# 02_CM4_Module.net
KiCad netlist of a schematic drawn in Altium Designer
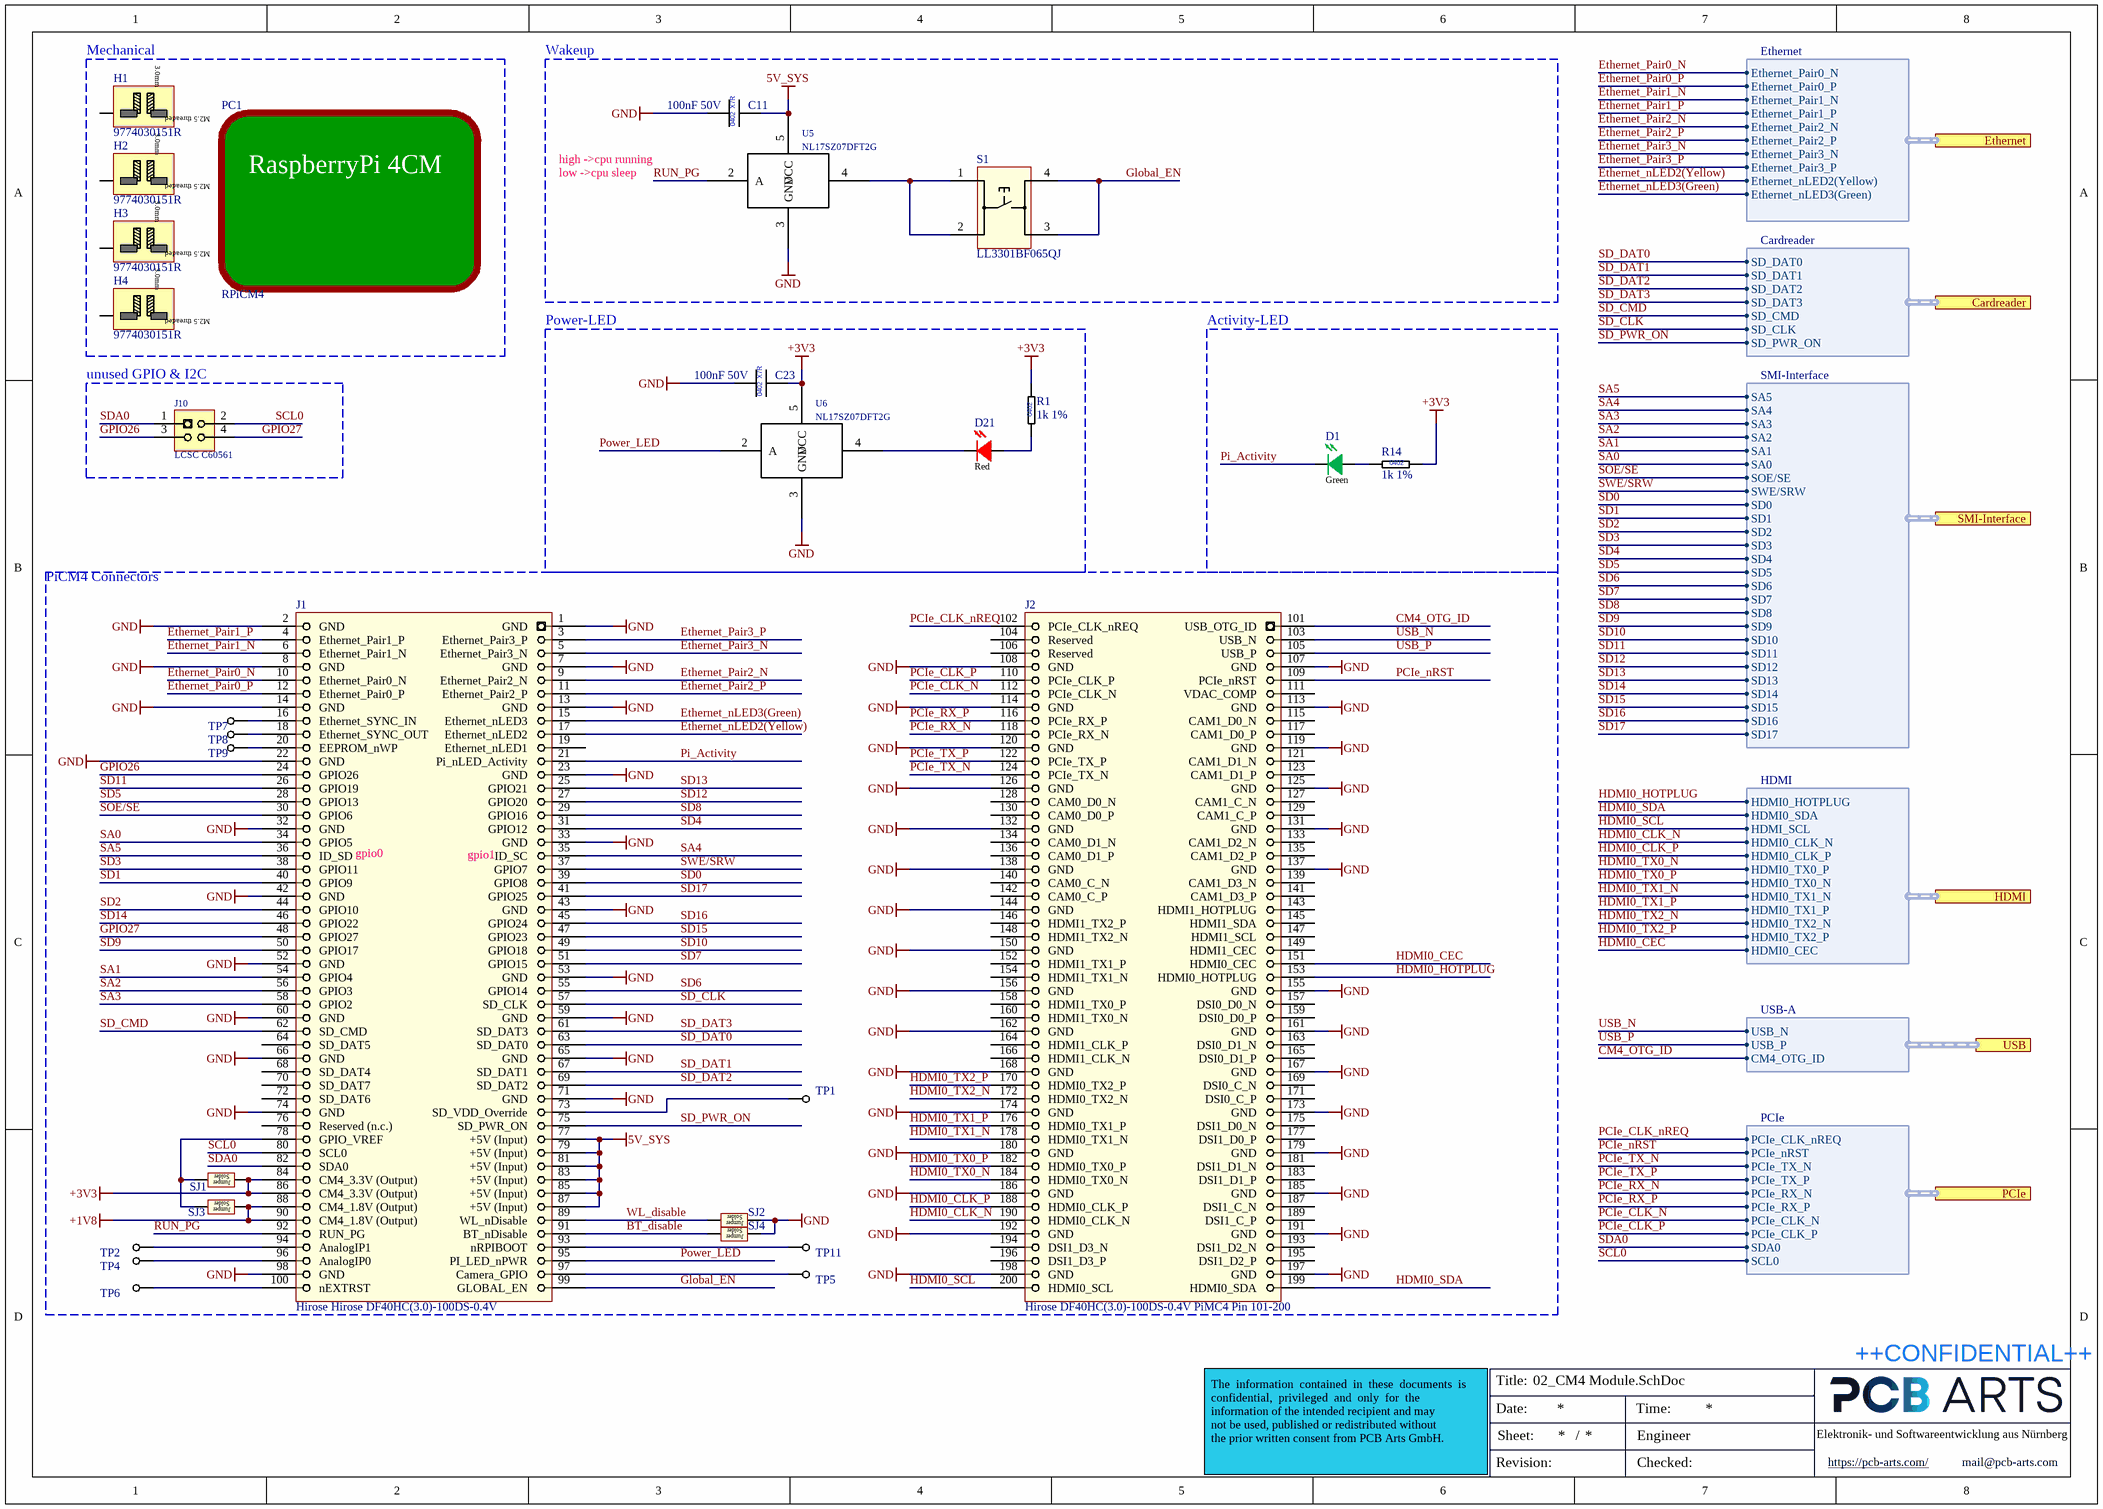
[diagram p0: 02_CM4 Module.SchDoc]

(export (version "E")
  (design (tool "Eeschema 10.0.6"))
  (components
    (comp (ref "C11")
      (value "100nF 50V")
      (footprint "AlemNano 201029:CAP_0402")
      (description "Multilayer Ceramic Capacitors MLCC - SMD/SMT 0402 50VDC")
      (libsource (lib "AlemNano 201029") (part "CAP_0402_100nF_50V"))
    )
    (comp (ref "C23")
      (value "100nF 50V")
      (footprint "AlemNano 201029:CAP_0402")
      (description "Multilayer Ceramic Capacitors MLCC - SMD/SMT 0402 50VDC")
      (libsource (lib "AlemNano 201029") (part "CAP_0402_100nF_50V"))
    )
    (comp (ref "D1")
      (value "LTST-S270KGKT")
      (footprint "Active:LED-0603 Sideview")
      (description "GREEN  0603 Light Emitting Diode")
      (fields (field (name "COLOR") "Green"))
      (libsource (lib "Active") (part "LED 0603 Green Sideview"))
    )
    (comp (ref "D21")
      (value "LTST-S270KRKT")
      (footprint "Active:LED-0603 Sideview")
      (description "RED  0603 Light Emitting Diode")
      (fields (field (name "COLOR") "Red"))
      (libsource (lib "Active") (part "LED 0603 Red Sideview"))
    )
    (comp (ref "H1")
      (value "9774030151R")
      (footprint "Electro_Mech:9774030151R")
      (description "Würth Standoff M2.5 h:3.0mm 9774030151R")
      (libsource (lib "Electro_Mech") (part "Würth Standoff M2.5 h{colon}3.0mm"))
    )
    (comp (ref "H2")
      (value "9774030151R")
      (footprint "Electro_Mech:9774030151R")
      (description "Würth Standoff M2.5 h:3.0mm 9774030151R")
      (libsource (lib "Electro_Mech") (part "Würth Standoff M2.5 h{colon}3.0mm"))
    )
    (comp (ref "H3")
      (value "9774030151R")
      (footprint "Electro_Mech:9774030151R")
      (description "Würth Standoff M2.5 h:3.0mm 9774030151R")
      (libsource (lib "Electro_Mech") (part "Würth Standoff M2.5 h{colon}3.0mm"))
    )
    (comp (ref "H4")
      (value "9774030151R")
      (footprint "Electro_Mech:9774030151R")
      (description "Würth Standoff M2.5 h:3.0mm 9774030151R")
      (libsource (lib "Electro_Mech") (part "Würth Standoff M2.5 h{colon}3.0mm"))
    )
    (comp (ref "J1")
      (value "Hirose Hirose DF40HC(3.0)-100DS-0.4V")
      (footprint "conn:Hirose DF40HC(3.0)-100DS-0.4V_1-100")
      (description "Hirose DF40HC(3.0)-100DS-0.4V 3mm heigth receptacle for Raspberry Pi CM4, Pin 1-100")
      (libsource (lib "Conn") (part "DF40HC(3.0)-100DS-0.4V RPiCM4 Pin 1-100"))
    )
    (comp (ref "J2")
      (value "Hirose DF40HC(3.0)-100DS-0.4V PiMC4 Pin 101-200")
      (footprint "Conn:Hirose DF40HC(3.0)-100DS-0.4V_PiCM4_101_200")
      (description "Hirose DF40C-100DS-0.4V 3mm heigth receptacle for Raspberry Pi CM4, Pin 101-200")
      (libsource (lib "Conn") (part "DF40HC(3.0)-100DS-0.4V RPiCM4 Pin 101-200"))
    )
    (comp (ref "J10")
      (value "LCSC C60561")
      (footprint "conn:LCSC C60561")
      (description "Pin header 2.54mm 4Pol right angle")
      (libsource (lib "Conn") (part "LCSC C60561_Pin header 2.54mm 4Pol right angle"))
    )
    (comp (ref "PC1")
      (value "RPiCM4")
      (footprint "Mechanical:RaspberryPi_CM4")
      (description "Raspberry Pi 4 Compute Module 4")
      (libsource (lib "Mechanical") (part "Raspberry Pi Compute Module 4"))
    )
    (comp (ref "R1")
      (value "1k 1%")
      (footprint "res:RES_0402")
      (description "Thick Film Resistors - SMD 1kOhm 1%")
      (libsource (lib "Res") (part "RES_0402_1k_1%"))
    )
    (comp (ref "R14")
      (value "1k 1%")
      (footprint "res:RES_0402")
      (description "Thick Film Resistors - SMD 1kOhm 1%")
      (libsource (lib "Res") (part "RES_0402_1k_1%"))
    )
    (comp (ref "S1")
      (value "LL3301BF065QJ")
      (footprint "Electro_Mech:LL3301BF065QJ")
      (description "SPST Top Actuated  Button, 65gf, SMD h: 9.8mm")
      (libsource (lib "Electro_Mech") (part "LL3301BF065QJ_SPST Top Actuated  Button, 65gf, SMD h{colon} 9.8mm"))
    )
    (comp (ref "SJ1")
      (value "Solderbridge_0402")
      (footprint "Conn:Solderbridge_0402")
      (libsource (lib "Conn") (part "Solderbridge_0402"))
    )
    (comp (ref "SJ2")
      (value "Solderbridge_0402")
      (footprint "Conn:Solderbridge_0402")
      (libsource (lib "Conn") (part "Solderbridge_0402"))
    )
    (comp (ref "SJ3")
      (value "Solderbridge_0402")
      (footprint "Conn:Solderbridge_0402")
      (libsource (lib "Conn") (part "Solderbridge_0402"))
    )
    (comp (ref "SJ4")
      (value "Solderbridge_0402")
      (footprint "Conn:Solderbridge_0402")
      (libsource (lib "Conn") (part "Solderbridge_0402"))
    )
    (comp (ref "TP1")
      (value "Testpoint")
      (footprint "Electro_mech:Testpoint 0.8mm")
      (description "Testpoint 0.8mm")
      (libsource (lib "Electro_Mech") (part "Testpoint 0.8mm"))
    )
    (comp (ref "TP2")
      (value "Testpoint")
      (footprint "Electro_mech:Testpoint 0.8mm")
      (description "Testpoint 0.8mm")
      (libsource (lib "Electro_Mech") (part "Testpoint 0.8mm"))
    )
    (comp (ref "TP4")
      (value "Testpoint")
      (footprint "Electro_mech:Testpoint 0.8mm")
      (description "Testpoint 0.8mm")
      (libsource (lib "Electro_Mech") (part "Testpoint 0.8mm"))
    )
    (comp (ref "TP5")
      (value "Testpoint")
      (footprint "Electro_mech:Testpoint 0.8mm")
      (description "Testpoint 0.8mm")
      (libsource (lib "Electro_Mech") (part "Testpoint 0.8mm"))
    )
    (comp (ref "TP6")
      (value "Testpoint")
      (footprint "Electro_mech:Testpoint 0.8mm")
      (description "Testpoint 0.8mm")
      (libsource (lib "Electro_Mech") (part "Testpoint 0.8mm"))
    )
    (comp (ref "TP7")
      (value "Testpoint")
      (footprint "Electro_mech:Testpoint 0.8mm")
      (description "Testpoint 0.8mm")
      (libsource (lib "Electro_Mech") (part "Testpoint 0.8mm"))
    )
    (comp (ref "TP8")
      (value "Testpoint")
      (footprint "Electro_mech:Testpoint 0.8mm")
      (description "Testpoint 0.8mm")
      (libsource (lib "Electro_Mech") (part "Testpoint 0.8mm"))
    )
    (comp (ref "TP9")
      (value "Testpoint")
      (footprint "Electro_mech:Testpoint 0.8mm")
      (description "Testpoint 0.8mm")
      (libsource (lib "Electro_Mech") (part "Testpoint 0.8mm"))
    )
    (comp (ref "TP11")
      (value "Testpoint")
      (footprint "Electro_mech:Testpoint 0.8mm")
      (description "Testpoint 0.8mm")
      (libsource (lib "Electro_Mech") (part "Testpoint 0.8mm"))
    )
    (comp (ref "U5")
      (value "NL17SZ07DFT2G")
      (footprint "Digital:SOT65P210X110-5N")
      (description "Puffer u. Leitungstreiber 1.65-5.5V Single Non-Inverting")
      (libsource (lib "Digital") (part "NL17SZ07DFT2G_Buffer 1.65-5.5V Single Non-Inverting"))
    )
    (comp (ref "U6")
      (value "NL17SZ07DFT2G")
      (footprint "Digital:SOT65P210X110-5N")
      (description "Puffer u. Leitungstreiber 1.65-5.5V Single Non-Inverting")
      (libsource (lib "Digital") (part "NL17SZ07DFT2G_Buffer 1.65-5.5V Single Non-Inverting"))
    )
  )
  (nets
    (net (code "7") (name "+1V8") (class "Default")
      (node (ref "J1") (pin "88") (pinfunction "CM4_1.8V_(Output)_88") (pintype "passive"))
      (node (ref "J1") (pin "90") (pinfunction "CM4_1.8V_(Output)_90") (pintype "passive"))
      (node (ref "SJ3") (pin "2") (pinfunction "2_2") (pintype "passive"))
    )
    (net (code "8") (name "+3V3") (class "Default")
      (node (ref "C23") (pin "2") (pinfunction "2_2") (pintype "passive"))
      (node (ref "J1") (pin "84") (pinfunction "CM4_3.3V_(Output)_84") (pintype "passive"))
      (node (ref "J1") (pin "86") (pinfunction "CM4_3.3V_(Output)_86") (pintype "passive"))
      (node (ref "R1") (pin "2") (pinfunction "2_2") (pintype "passive"))
      (node (ref "R14") (pin "2") (pinfunction "2_2") (pintype "passive"))
      (node (ref "SJ1") (pin "2") (pinfunction "2_2") (pintype "passive"))
      (node (ref "U6") (pin "5") (pinfunction "VCC_5") (pintype "passive"))
    )
    (net (code "9") (name "/BT_disable") (class "Default")
      (node (ref "J1") (pin "91") (pinfunction "BT_nDisable_91") (pintype "passive"))
      (node (ref "SJ4") (pin "1") (pinfunction "1_1") (pintype "passive"))
    )
    (net (code "10") (name "/CM4_OTG_ID") (class "Default")
      (node (ref "J2") (pin "101") (pinfunction "USB_OTG_ID_101") (pintype "passive"))
    )
    (net (code "11") (name "/Ethernet_Pair0_N") (class "Default")
      (node (ref "J1") (pin "10") (pinfunction "Ethernet_Pair0_N_10") (pintype "passive"))
    )
    (net (code "12") (name "/Ethernet_Pair0_P") (class "Default")
      (node (ref "J1") (pin "12") (pinfunction "Ethernet_Pair0_P_12") (pintype "passive"))
    )
    (net (code "13") (name "/Ethernet_Pair1_N") (class "Default")
      (node (ref "J1") (pin "6") (pinfunction "Ethernet_Pair1_N_6") (pintype "passive"))
    )
    (net (code "14") (name "/Ethernet_Pair1_P") (class "Default")
      (node (ref "J1") (pin "4") (pinfunction "Ethernet_Pair1_P_4") (pintype "passive"))
    )
    (net (code "15") (name "/Ethernet_Pair2_N") (class "Default")
      (node (ref "J1") (pin "9") (pinfunction "Ethernet_Pair2_N_9") (pintype "passive"))
    )
    (net (code "16") (name "/Ethernet_Pair2_P") (class "Default")
      (node (ref "J1") (pin "11") (pinfunction "Ethernet_Pair2_P_11") (pintype "passive"))
    )
    (net (code "17") (name "/Ethernet_Pair3_N") (class "Default")
      (node (ref "J1") (pin "5") (pinfunction "Ethernet_Pair3_N_5") (pintype "passive"))
    )
    (net (code "18") (name "/Ethernet_Pair3_P") (class "Default")
      (node (ref "J1") (pin "3") (pinfunction "Ethernet_Pair3_P_3") (pintype "passive"))
    )
    (net (code "19") (name "/Ethernet_nLED2(Yellow)") (class "Default")
      (node (ref "J1") (pin "17") (pinfunction "Ethernet_nLED2_17") (pintype "passive"))
    )
    (net (code "20") (name "/Ethernet_nLED3(Green)") (class "Default")
      (node (ref "J1") (pin "15") (pinfunction "Ethernet_nLED3_15") (pintype "passive"))
    )
    (net (code "21") (name "/GPIO26") (class "Default")
      (node (ref "J1") (pin "24") (pinfunction "GPIO26_24") (pintype "passive"))
      (node (ref "J10") (pin "3") (pinfunction "3_3") (pintype "passive"))
    )
    (net (code "22") (name "/GPIO27") (class "Default")
      (node (ref "J1") (pin "48") (pinfunction "GPIO27_48") (pintype "passive"))
      (node (ref "J10") (pin "4") (pinfunction "4_4") (pintype "passive"))
    )
    (net (code "23") (name "/Global_EN") (class "Default")
      (node (ref "J1") (pin "99") (pinfunction "GLOBAL_EN_99") (pintype "passive"))
      (node (ref "S1") (pin "3") (pinfunction "3_3") (pintype "passive"))
      (node (ref "S1") (pin "4") (pinfunction "4_4") (pintype "passive"))
    )
    (net (code "24") (name "/HDMI0_CEC") (class "Default")
      (node (ref "J2") (pin "151") (pinfunction "HDMI0_CEC_151") (pintype "passive"))
    )
    (net (code "25") (name "/HDMI0_CLK_N") (class "Default")
      (node (ref "J2") (pin "190") (pinfunction "HDMI0_CLK_N_190") (pintype "passive"))
    )
    (net (code "26") (name "/HDMI0_CLK_P") (class "Default")
      (node (ref "J2") (pin "188") (pinfunction "HDMI0_CLK_P_188") (pintype "passive"))
    )
    (net (code "27") (name "/HDMI0_HOTPLUG") (class "Default")
      (node (ref "J2") (pin "153") (pinfunction "HDMI0_HOTPLUG_153") (pintype "passive"))
    )
    (net (code "28") (name "/HDMI0_SCL") (class "Default")
      (node (ref "J2") (pin "200") (pinfunction "HDMI0_SCL_200") (pintype "passive"))
    )
    (net (code "29") (name "/HDMI0_SDA") (class "Default")
      (node (ref "J2") (pin "199") (pinfunction "HDMI0_SDA_199") (pintype "passive"))
    )
    (net (code "30") (name "/HDMI0_TX0_N") (class "Default")
      (node (ref "J2") (pin "184") (pinfunction "HDMI0_TX0_N_184") (pintype "passive"))
    )
    (net (code "31") (name "/HDMI0_TX0_P") (class "Default")
      (node (ref "J2") (pin "182") (pinfunction "HDMI0_TX0_P_182") (pintype "passive"))
    )
    (net (code "32") (name "/HDMI0_TX1_N") (class "Default")
      (node (ref "J2") (pin "178") (pinfunction "HDMI0_TX1_N_178") (pintype "passive"))
    )
    (net (code "33") (name "/HDMI0_TX1_P") (class "Default")
      (node (ref "J2") (pin "176") (pinfunction "HDMI0_TX1_P_176") (pintype "passive"))
    )
    (net (code "34") (name "/HDMI0_TX2_N") (class "Default")
      (node (ref "J2") (pin "172") (pinfunction "HDMI0_TX2_N_172") (pintype "passive"))
    )
    (net (code "35") (name "/HDMI0_TX2_P") (class "Default")
      (node (ref "J2") (pin "170") (pinfunction "HDMI0_TX2_P_170") (pintype "passive"))
    )
    (net (code "36") (name "/PCIe_CLK_N") (class "Default")
      (node (ref "J2") (pin "112") (pinfunction "PCIe_CLK_N_112") (pintype "passive"))
    )
    (net (code "37") (name "/PCIe_CLK_P") (class "Default")
      (node (ref "J2") (pin "110") (pinfunction "PCIe_CLK_P_110") (pintype "passive"))
    )
    (net (code "38") (name "/PCIe_CLK_nREQ") (class "Default")
      (node (ref "J2") (pin "102") (pinfunction "PCIe_CLK_nREQ_102") (pintype "passive"))
    )
    (net (code "39") (name "/PCIe_RX_N") (class "Default")
      (node (ref "J2") (pin "118") (pinfunction "PCIe_RX_N_118") (pintype "passive"))
    )
    (net (code "40") (name "/PCIe_RX_P") (class "Default")
      (node (ref "J2") (pin "116") (pinfunction "PCIe_RX_P_116") (pintype "passive"))
    )
    (net (code "41") (name "/PCIe_TX_N") (class "Default")
      (node (ref "J2") (pin "124") (pinfunction "PCIe_TX_N_124") (pintype "passive"))
    )
    (net (code "42") (name "/PCIe_TX_P") (class "Default")
      (node (ref "J2") (pin "122") (pinfunction "PCIe_TX_P_122") (pintype "passive"))
    )
    (net (code "43") (name "/PCIe_nRST") (class "Default")
      (node (ref "J2") (pin "109") (pinfunction "PCIe_nRST_109") (pintype "passive"))
    )
    (net (code "44") (name "/Pi_Activity") (class "Default")
      (node (ref "D1") (pin "1") (pinfunction "1_1") (pintype "passive"))
      (node (ref "J1") (pin "21") (pinfunction "Pi_nLED_Activity_21") (pintype "passive"))
    )
    (net (code "45") (name "/Power_LED") (class "Default")
      (node (ref "J1") (pin "95") (pinfunction "PI_LED_nPWR_95") (pintype "passive"))
      (node (ref "U6") (pin "2") (pinfunction "A_2") (pintype "passive"))
    )
    (net (code "46") (name "/RUN_PG") (class "Default")
      (node (ref "J1") (pin "92") (pinfunction "RUN_PG_92") (pintype "passive"))
      (node (ref "U5") (pin "2") (pinfunction "A_2") (pintype "passive"))
    )
    (net (code "47") (name "/SA0") (class "Default")
      (node (ref "J1") (pin "34") (pinfunction "GPIO5_34") (pintype "passive"))
    )
    (net (code "48") (name "/SA1") (class "Default")
      (node (ref "J1") (pin "54") (pinfunction "GPIO4_54") (pintype "passive"))
    )
    (net (code "49") (name "/SA2") (class "Default")
      (node (ref "J1") (pin "56") (pinfunction "GPIO3_56") (pintype "passive"))
    )
    (net (code "50") (name "/SA3") (class "Default")
      (node (ref "J1") (pin "58") (pinfunction "GPIO2_58") (pintype "passive"))
    )
    (net (code "51") (name "/SA4") (class "Default")
      (node (ref "J1") (pin "35") (pinfunction "ID_SC_35") (pintype "passive"))
    )
    (net (code "52") (name "/SA5") (class "Default")
      (node (ref "J1") (pin "36") (pinfunction "ID_SD_36") (pintype "passive"))
    )
    (net (code "53") (name "/SCL0") (class "Default")
      (node (ref "J1") (pin "80") (pinfunction "SCL0_80") (pintype "passive"))
      (node (ref "J10") (pin "2") (pinfunction "2_2") (pintype "passive"))
    )
    (net (code "54") (name "/SD0") (class "Default")
      (node (ref "J1") (pin "39") (pinfunction "GPIO8_39") (pintype "passive"))
    )
    (net (code "55") (name "/SD1") (class "Default")
      (node (ref "J1") (pin "40") (pinfunction "GPIO9_40") (pintype "passive"))
    )
    (net (code "56") (name "/SD2") (class "Default")
      (node (ref "J1") (pin "44") (pinfunction "GPIO10_44") (pintype "passive"))
    )
    (net (code "57") (name "/SD3") (class "Default")
      (node (ref "J1") (pin "38") (pinfunction "GPIO11_38") (pintype "passive"))
    )
    (net (code "58") (name "/SD4") (class "Default")
      (node (ref "J1") (pin "31") (pinfunction "GPIO12_31") (pintype "passive"))
    )
    (net (code "59") (name "/SD5") (class "Default")
      (node (ref "J1") (pin "28") (pinfunction "GPIO13_28") (pintype "passive"))
    )
    (net (code "60") (name "/SD6") (class "Default")
      (node (ref "J1") (pin "55") (pinfunction "GPIO14_55") (pintype "passive"))
    )
    (net (code "61") (name "/SD7") (class "Default")
      (node (ref "J1") (pin "51") (pinfunction "GPIO15_51") (pintype "passive"))
    )
    (net (code "62") (name "/SD8") (class "Default")
      (node (ref "J1") (pin "29") (pinfunction "GPIO16_29") (pintype "passive"))
    )
    (net (code "63") (name "/SD9") (class "Default")
      (node (ref "J1") (pin "50") (pinfunction "GPIO17_50") (pintype "passive"))
    )
    (net (code "64") (name "/SD10") (class "Default")
      (node (ref "J1") (pin "49") (pinfunction "GPIO18_49") (pintype "passive"))
    )
    (net (code "65") (name "/SD11") (class "Default")
      (node (ref "J1") (pin "26") (pinfunction "GPIO19_26") (pintype "passive"))
    )
    (net (code "66") (name "/SD12") (class "Default")
      (node (ref "J1") (pin "27") (pinfunction "GPIO20_27") (pintype "passive"))
    )
    (net (code "67") (name "/SD13") (class "Default")
      (node (ref "J1") (pin "25") (pinfunction "GPIO21_25") (pintype "passive"))
    )
    (net (code "68") (name "/SD14") (class "Default")
      (node (ref "J1") (pin "46") (pinfunction "GPIO22_46") (pintype "passive"))
    )
    (net (code "69") (name "/SD15") (class "Default")
      (node (ref "J1") (pin "47") (pinfunction "GPIO23_47") (pintype "passive"))
    )
    (net (code "70") (name "/SD16") (class "Default")
      (node (ref "J1") (pin "45") (pinfunction "GPIO24_45") (pintype "passive"))
    )
    (net (code "71") (name "/SD17") (class "Default")
      (node (ref "J1") (pin "41") (pinfunction "GPIO25_41") (pintype "passive"))
    )
    (net (code "72") (name "/SDA0") (class "Default")
      (node (ref "J1") (pin "82") (pinfunction "SDA0_82") (pintype "passive"))
      (node (ref "J10") (pin "1") (pinfunction "1_1") (pintype "passive"))
    )
    (net (code "73") (name "/SD_CLK") (class "Default")
      (node (ref "J1") (pin "57") (pinfunction "SD_CLK_57") (pintype "passive"))
    )
    (net (code "74") (name "/SD_CMD") (class "Default")
      (node (ref "J1") (pin "62") (pinfunction "SD_CMD_62") (pintype "passive"))
    )
    (net (code "75") (name "/SD_DAT0") (class "Default")
      (node (ref "J1") (pin "63") (pinfunction "SD_DAT0_63") (pintype "passive"))
    )
    (net (code "76") (name "/SD_DAT1") (class "Default")
      (node (ref "J1") (pin "67") (pinfunction "SD_DAT1_67") (pintype "passive"))
    )
    (net (code "77") (name "/SD_DAT2") (class "Default")
      (node (ref "J1") (pin "69") (pinfunction "SD_DAT2_69") (pintype "passive"))
    )
    (net (code "78") (name "/SD_DAT3") (class "Default")
      (node (ref "J1") (pin "61") (pinfunction "SD_DAT3_61") (pintype "passive"))
    )
    (net (code "79") (name "/SD_PWR_ON") (class "Default")
      (node (ref "J1") (pin "75") (pinfunction "SD_PWR_ON_75") (pintype "passive"))
    )
    (net (code "80") (name "/SOE{slash}SE") (class "Default")
      (node (ref "J1") (pin "30") (pinfunction "GPIO6_30") (pintype "passive"))
    )
    (net (code "81") (name "/SWE{slash}SRW") (class "Default")
      (node (ref "J1") (pin "37") (pinfunction "GPIO7_37") (pintype "passive"))
    )
    (net (code "82") (name "/USB_N") (class "Default")
      (node (ref "J2") (pin "103") (pinfunction "USB_N_103") (pintype "passive"))
    )
    (net (code "83") (name "/USB_P") (class "Default")
      (node (ref "J2") (pin "105") (pinfunction "USB_P_105") (pintype "passive"))
    )
    (net (code "84") (name "/WL_disable") (class "Default")
      (node (ref "J1") (pin "89") (pinfunction "WL_nDisable_89") (pintype "passive"))
      (node (ref "SJ2") (pin "1") (pinfunction "1_1") (pintype "passive"))
    )
    (net (code "91") (name "5V_SYS") (class "Default")
      (node (ref "C11") (pin "2") (pinfunction "2_2") (pintype "passive"))
      (node (ref "J1") (pin "77") (pinfunction "+5V_(Input)_77") (pintype "passive"))
      (node (ref "J1") (pin "79") (pinfunction "+5V_(Input)_79") (pintype "passive"))
      (node (ref "J1") (pin "81") (pinfunction "+5V_(Input)_81") (pintype "passive"))
      (node (ref "J1") (pin "83") (pinfunction "+5V_(Input)_83") (pintype "passive"))
      (node (ref "J1") (pin "85") (pinfunction "+5V_(Input)_85") (pintype "passive"))
      (node (ref "J1") (pin "87") (pinfunction "+5V_(Input)_87") (pintype "passive"))
      (node (ref "U5") (pin "5") (pinfunction "VCC_5") (pintype "passive"))
    )
    (net (code "92") (name "GND") (class "Default")
      (node (ref "C11") (pin "1") (pinfunction "1_1") (pintype "passive"))
      (node (ref "C23") (pin "1") (pinfunction "1_1") (pintype "passive"))
      (node (ref "J1") (pin "1") (pinfunction "GND_1") (pintype "passive"))
      (node (ref "J1") (pin "13") (pinfunction "GND_13") (pintype "passive"))
      (node (ref "J1") (pin "14") (pinfunction "GND_14") (pintype "passive"))
      (node (ref "J1") (pin "2") (pinfunction "GND_2") (pintype "passive"))
      (node (ref "J1") (pin "22") (pinfunction "GND_22") (pintype "passive"))
      (node (ref "J1") (pin "23") (pinfunction "GND_23") (pintype "passive"))
      (node (ref "J1") (pin "32") (pinfunction "GND_32") (pintype "passive"))
      (node (ref "J1") (pin "33") (pinfunction "GND_33") (pintype "passive"))
      (node (ref "J1") (pin "42") (pinfunction "GND_42") (pintype "passive"))
      (node (ref "J1") (pin "43") (pinfunction "GND_43") (pintype "passive"))
      (node (ref "J1") (pin "52") (pinfunction "GND_52") (pintype "passive"))
      (node (ref "J1") (pin "53") (pinfunction "GND_53") (pintype "passive"))
      (node (ref "J1") (pin "59") (pinfunction "GND_59") (pintype "passive"))
      (node (ref "J1") (pin "60") (pinfunction "GND_60") (pintype "passive"))
      (node (ref "J1") (pin "65") (pinfunction "GND_65") (pintype "passive"))
      (node (ref "J1") (pin "66") (pinfunction "GND_66") (pintype "passive"))
      (node (ref "J1") (pin "7") (pinfunction "GND_7") (pintype "passive"))
      (node (ref "J1") (pin "71") (pinfunction "GND_71") (pintype "passive"))
      (node (ref "J1") (pin "74") (pinfunction "GND_74") (pintype "passive"))
      (node (ref "J1") (pin "8") (pinfunction "GND_8") (pintype "passive"))
      (node (ref "J1") (pin "98") (pinfunction "GND_98") (pintype "passive"))
      (node (ref "J2") (pin "107") (pinfunction "GND_107") (pintype "passive"))
      (node (ref "J2") (pin "108") (pinfunction "GND_108") (pintype "passive"))
      (node (ref "J2") (pin "113") (pinfunction "GND_113") (pintype "passive"))
      (node (ref "J2") (pin "114") (pinfunction "GND_114") (pintype "passive"))
      (node (ref "J2") (pin "119") (pinfunction "GND_119") (pintype "passive"))
      (node (ref "J2") (pin "120") (pinfunction "GND_120") (pintype "passive"))
      (node (ref "J2") (pin "125") (pinfunction "GND_125") (pintype "passive"))
      (node (ref "J2") (pin "126") (pinfunction "GND_126") (pintype "passive"))
      (node (ref "J2") (pin "131") (pinfunction "GND_131") (pintype "passive"))
      (node (ref "J2") (pin "132") (pinfunction "GND_132") (pintype "passive"))
      (node (ref "J2") (pin "137") (pinfunction "GND_137") (pintype "passive"))
      (node (ref "J2") (pin "138") (pinfunction "GND_138") (pintype "passive"))
      (node (ref "J2") (pin "144") (pinfunction "GND_144") (pintype "passive"))
      (node (ref "J2") (pin "150") (pinfunction "GND_150") (pintype "passive"))
      (node (ref "J2") (pin "155") (pinfunction "GND_155") (pintype "passive"))
      (node (ref "J2") (pin "156") (pinfunction "GND_156") (pintype "passive"))
      (node (ref "J2") (pin "161") (pinfunction "GND_161") (pintype "passive"))
      (node (ref "J2") (pin "162") (pinfunction "GND_162") (pintype "passive"))
      (node (ref "J2") (pin "167") (pinfunction "GND_167") (pintype "passive"))
      (node (ref "J2") (pin "168") (pinfunction "GND_168") (pintype "passive"))
      (node (ref "J2") (pin "173") (pinfunction "GND_173") (pintype "passive"))
      (node (ref "J2") (pin "174") (pinfunction "GND_174") (pintype "passive"))
      (node (ref "J2") (pin "179") (pinfunction "GND_179") (pintype "passive"))
      (node (ref "J2") (pin "180") (pinfunction "GND_180") (pintype "passive"))
      (node (ref "J2") (pin "185") (pinfunction "GND_185") (pintype "passive"))
      (node (ref "J2") (pin "186") (pinfunction "GND_186") (pintype "passive"))
      (node (ref "J2") (pin "191") (pinfunction "GND_191") (pintype "passive"))
      (node (ref "J2") (pin "192") (pinfunction "GND_192") (pintype "passive"))
      (node (ref "J2") (pin "197") (pinfunction "GND_197") (pintype "passive"))
      (node (ref "J2") (pin "198") (pinfunction "GND_198") (pintype "passive"))
      (node (ref "SJ2") (pin "2") (pinfunction "2_2") (pintype "passive"))
      (node (ref "SJ4") (pin "2") (pinfunction "2_2") (pintype "passive"))
      (node (ref "U5") (pin "3") (pinfunction "GND_3") (pintype "passive"))
      (node (ref "U6") (pin "3") (pinfunction "GND_3") (pintype "passive"))
    )
    (net (code "93") (name "Net-(D1-Pad2)") (class "Default")
      (node (ref "D1") (pin "2") (pinfunction "2_2") (pintype "passive"))
      (node (ref "R14") (pin "1") (pinfunction "1_1") (pintype "passive"))
    )
    (net (code "94") (name "Net-(D21-Pad2)") (class "Default")
      (node (ref "D21") (pin "2") (pinfunction "2_2") (pintype "passive"))
      (node (ref "R1") (pin "1") (pinfunction "1_1") (pintype "passive"))
    )
    (net (code "95") (name "Net-(J1-AnalogIP0)") (class "Default")
      (node (ref "J1") (pin "96") (pinfunction "AnalogIP0_96") (pintype "passive"))
      (node (ref "TP4") (pin "1") (pinfunction "GND_1") (pintype "passive"))
    )
    (net (code "96") (name "Net-(J1-AnalogIP1)") (class "Default")
      (node (ref "J1") (pin "94") (pinfunction "AnalogIP1_94") (pintype "passive"))
      (node (ref "TP2") (pin "1") (pinfunction "GND_1") (pintype "passive"))
    )
    (net (code "97") (name "Net-(J1-Camera_GPIO)") (class "Default")
      (node (ref "J1") (pin "97") (pinfunction "Camera_GPIO_97") (pintype "passive"))
      (node (ref "TP5") (pin "1") (pinfunction "GND_1") (pintype "passive"))
    )
    (net (code "98") (name "Net-(J1-EEPROM_nWP)") (class "Default")
      (node (ref "J1") (pin "20") (pinfunction "EEPROM_nWP_20") (pintype "passive"))
      (node (ref "TP9") (pin "1") (pinfunction "GND_1") (pintype "passive"))
    )
    (net (code "99") (name "Net-(J1-Ethernet_SYNC_IN)") (class "Default")
      (node (ref "J1") (pin "16") (pinfunction "Ethernet_SYNC_IN_16") (pintype "passive"))
      (node (ref "TP7") (pin "1") (pinfunction "GND_1") (pintype "passive"))
    )
    (net (code "100") (name "Net-(J1-Ethernet_SYNC_OUT)") (class "Default")
      (node (ref "J1") (pin "18") (pinfunction "Ethernet_SYNC_OUT_18") (pintype "passive"))
      (node (ref "TP8") (pin "1") (pinfunction "GND_1") (pintype "passive"))
    )
    (net (code "101") (name "Net-(J1-GPIO_VREF)") (class "Default")
      (node (ref "J1") (pin "78") (pinfunction "GPIO_VREF_78") (pintype "passive"))
      (node (ref "SJ1") (pin "1") (pinfunction "1_1") (pintype "passive"))
      (node (ref "SJ3") (pin "1") (pinfunction "1_1") (pintype "passive"))
    )
    (net (code "102") (name "Net-(J1-SD_VDD_Override)") (class "Default")
      (node (ref "J1") (pin "73") (pinfunction "SD_VDD_Override_73") (pintype "passive"))
      (node (ref "TP1") (pin "1") (pinfunction "GND_1") (pintype "passive"))
    )
    (net (code "103") (name "Net-(J1-nEXTRST)") (class "Default")
      (node (ref "J1") (pin "100") (pinfunction "nEXTRST_100") (pintype "passive"))
      (node (ref "TP6") (pin "1") (pinfunction "GND_1") (pintype "passive"))
    )
    (net (code "104") (name "Net-(J1-nRPIBOOT)") (class "Default")
      (node (ref "J1") (pin "93") (pinfunction "nRPIBOOT_93") (pintype "passive"))
      (node (ref "TP11") (pin "1") (pinfunction "GND_1") (pintype "passive"))
    )
    (net (code "105") (name "Net-(U5-Y)") (class "Default")
      (node (ref "S1") (pin "1") (pinfunction "1_1") (pintype "passive"))
      (node (ref "S1") (pin "2") (pinfunction "2_2") (pintype "passive"))
      (node (ref "U5") (pin "4") (pinfunction "Y_4") (pintype "passive"))
    )
    (net (code "106") (name "Net-(U6-Y)") (class "Default")
      (node (ref "D21") (pin "1") (pinfunction "1_1") (pintype "passive"))
      (node (ref "U6") (pin "4") (pinfunction "Y_4") (pintype "passive"))
    )
    (net (code "107") (name "unconnected-(H1-Pad1)") (class "Default")
      (node (ref "H1") (pin "1") (pinfunction "1_1") (pintype "passive"))
    )
    (net (code "108") (name "unconnected-(H2-Pad1)") (class "Default")
      (node (ref "H2") (pin "1") (pinfunction "1_1") (pintype "passive"))
    )
    (net (code "109") (name "unconnected-(H3-Pad1)") (class "Default")
      (node (ref "H3") (pin "1") (pinfunction "1_1") (pintype "passive"))
    )
    (net (code "110") (name "unconnected-(H4-Pad1)") (class "Default")
      (node (ref "H4") (pin "1") (pinfunction "1_1") (pintype "passive"))
    )
    (net (code "111") (name "unconnected-(J1-Ethernet_nLED1-Pad19)") (class "Default")
      (node (ref "J1") (pin "19") (pinfunction "Ethernet_nLED1_19") (pintype "passive"))
    )
    (net (code "112") (name "unconnected-(J1-Reserved_(n.c.)-Pad76)") (class "Default")
      (node (ref "J1") (pin "76") (pinfunction "Reserved_(n.c.)_76") (pintype "passive"))
    )
    (net (code "113") (name "unconnected-(J1-SD_DAT4-Pad68)") (class "Default")
      (node (ref "J1") (pin "68") (pinfunction "SD_DAT4_68") (pintype "passive"))
    )
    (net (code "114") (name "unconnected-(J1-SD_DAT5-Pad64)") (class "Default")
      (node (ref "J1") (pin "64") (pinfunction "SD_DAT5_64") (pintype "passive"))
    )
    (net (code "115") (name "unconnected-(J1-SD_DAT6-Pad72)") (class "Default")
      (node (ref "J1") (pin "72") (pinfunction "SD_DAT6_72") (pintype "passive"))
    )
    (net (code "116") (name "unconnected-(J1-SD_DAT7-Pad70)") (class "Default")
      (node (ref "J1") (pin "70") (pinfunction "SD_DAT7_70") (pintype "passive"))
    )
    (net (code "117") (name "unconnected-(J2-CAM0_C_N-Pad140)") (class "Default")
      (node (ref "J2") (pin "140") (pinfunction "CAM0_C_N_140") (pintype "passive"))
    )
    (net (code "118") (name "unconnected-(J2-CAM0_C_P-Pad142)") (class "Default")
      (node (ref "J2") (pin "142") (pinfunction "CAM0_C_P_142") (pintype "passive"))
    )
    (net (code "119") (name "unconnected-(J2-CAM0_D0_N-Pad128)") (class "Default")
      (node (ref "J2") (pin "128") (pinfunction "CAM0_D0_N_128") (pintype "passive"))
    )
    (net (code "120") (name "unconnected-(J2-CAM0_D0_P-Pad130)") (class "Default")
      (node (ref "J2") (pin "130") (pinfunction "CAM0_D0_P_130") (pintype "passive"))
    )
    (net (code "121") (name "unconnected-(J2-CAM0_D1_N-Pad134)") (class "Default")
      (node (ref "J2") (pin "134") (pinfunction "CAM0_D1_N_134") (pintype "passive"))
    )
    (net (code "122") (name "unconnected-(J2-CAM0_D1_P-Pad136)") (class "Default")
      (node (ref "J2") (pin "136") (pinfunction "CAM0_D1_P_136") (pintype "passive"))
    )
    (net (code "123") (name "unconnected-(J2-CAM1_C_N-Pad127)") (class "Default")
      (node (ref "J2") (pin "127") (pinfunction "CAM1_C_N_127") (pintype "passive"))
    )
    (net (code "124") (name "unconnected-(J2-CAM1_C_P-Pad129)") (class "Default")
      (node (ref "J2") (pin "129") (pinfunction "CAM1_C_P_129") (pintype "passive"))
    )
    (net (code "125") (name "unconnected-(J2-CAM1_D0_N-Pad115)") (class "Default")
      (node (ref "J2") (pin "115") (pinfunction "CAM1_D0_N_115") (pintype "passive"))
    )
    (net (code "126") (name "unconnected-(J2-CAM1_D0_P-Pad117)") (class "Default")
      (node (ref "J2") (pin "117") (pinfunction "CAM1_D0_P_117") (pintype "passive"))
    )
    (net (code "127") (name "unconnected-(J2-CAM1_D1_N-Pad121)") (class "Default")
      (node (ref "J2") (pin "121") (pinfunction "CAM1_D1_N_121") (pintype "passive"))
    )
    (net (code "128") (name "unconnected-(J2-CAM1_D1_P-Pad123)") (class "Default")
      (node (ref "J2") (pin "123") (pinfunction "CAM1_D1_P_123") (pintype "passive"))
    )
    (net (code "129") (name "unconnected-(J2-CAM1_D2_N-Pad133)") (class "Default")
      (node (ref "J2") (pin "133") (pinfunction "CAM1_D2_N_133") (pintype "passive"))
    )
    (net (code "130") (name "unconnected-(J2-CAM1_D2_P-Pad135)") (class "Default")
      (node (ref "J2") (pin "135") (pinfunction "CAM1_D2_P_135") (pintype "passive"))
    )
    (net (code "131") (name "unconnected-(J2-CAM1_D3_N-Pad139)") (class "Default")
      (node (ref "J2") (pin "139") (pinfunction "CAM1_D3_N_139") (pintype "passive"))
    )
    (net (code "132") (name "unconnected-(J2-CAM1_D3_P-Pad141)") (class "Default")
      (node (ref "J2") (pin "141") (pinfunction "CAM1_D3_P_141") (pintype "passive"))
    )
    (net (code "133") (name "unconnected-(J2-DSI0_C_N-Pad169)") (class "Default")
      (node (ref "J2") (pin "169") (pinfunction "DSI0_C_N_169") (pintype "passive"))
    )
    (net (code "134") (name "unconnected-(J2-DSI0_C_P-Pad171)") (class "Default")
      (node (ref "J2") (pin "171") (pinfunction "DSI0_C_P_171") (pintype "passive"))
    )
    (net (code "135") (name "unconnected-(J2-DSI0_D0_N-Pad157)") (class "Default")
      (node (ref "J2") (pin "157") (pinfunction "DSI0_D0_N_157") (pintype "passive"))
    )
    (net (code "136") (name "unconnected-(J2-DSI0_D0_P-Pad159)") (class "Default")
      (node (ref "J2") (pin "159") (pinfunction "DSI0_D0_P_159") (pintype "passive"))
    )
    (net (code "137") (name "unconnected-(J2-DSI0_D1_N-Pad163)") (class "Default")
      (node (ref "J2") (pin "163") (pinfunction "DSI0_D1_N_163") (pintype "passive"))
    )
    (net (code "138") (name "unconnected-(J2-DSI0_D1_P-Pad165)") (class "Default")
      (node (ref "J2") (pin "165") (pinfunction "DSI0_D1_P_165") (pintype "passive"))
    )
    (net (code "139") (name "unconnected-(J2-DSI1_C_N-Pad187)") (class "Default")
      (node (ref "J2") (pin "187") (pinfunction "DSI1_C_N_187") (pintype "passive"))
    )
    (net (code "140") (name "unconnected-(J2-DSI1_C_P-Pad189)") (class "Default")
      (node (ref "J2") (pin "189") (pinfunction "DSI1_C_P_189") (pintype "passive"))
    )
    (net (code "141") (name "unconnected-(J2-DSI1_D0_N-Pad175)") (class "Default")
      (node (ref "J2") (pin "175") (pinfunction "DSI1_D0_N_175") (pintype "passive"))
    )
    (net (code "142") (name "unconnected-(J2-DSI1_D0_P-Pad177)") (class "Default")
      (node (ref "J2") (pin "177") (pinfunction "DSI1_D0_P_177") (pintype "passive"))
    )
    (net (code "143") (name "unconnected-(J2-DSI1_D1_N-Pad181)") (class "Default")
      (node (ref "J2") (pin "181") (pinfunction "DSI1_D1_N_181") (pintype "passive"))
    )
    (net (code "144") (name "unconnected-(J2-DSI1_D1_P-Pad183)") (class "Default")
      (node (ref "J2") (pin "183") (pinfunction "DSI1_D1_P_183") (pintype "passive"))
    )
    (net (code "145") (name "unconnected-(J2-DSI1_D2_N-Pad193)") (class "Default")
      (node (ref "J2") (pin "193") (pinfunction "DSI1_D2_N_193") (pintype "passive"))
    )
    (net (code "146") (name "unconnected-(J2-DSI1_D2_P-Pad195)") (class "Default")
      (node (ref "J2") (pin "195") (pinfunction "DSI1_D2_P_195") (pintype "passive"))
    )
    (net (code "147") (name "unconnected-(J2-DSI1_D3_N-Pad194)") (class "Default")
      (node (ref "J2") (pin "194") (pinfunction "DSI1_D3_N_194") (pintype "passive"))
    )
    (net (code "148") (name "unconnected-(J2-DSI1_D3_P-Pad196)") (class "Default")
      (node (ref "J2") (pin "196") (pinfunction "DSI1_D3_P_196") (pintype "passive"))
    )
    (net (code "149") (name "unconnected-(J2-HDMI1_CEC-Pad149)") (class "Default")
      (node (ref "J2") (pin "149") (pinfunction "HDMI1_CEC_149") (pintype "passive"))
    )
    (net (code "150") (name "unconnected-(J2-HDMI1_CLK_N-Pad166)") (class "Default")
      (node (ref "J2") (pin "166") (pinfunction "HDMI1_CLK_N_166") (pintype "passive"))
    )
    (net (code "151") (name "unconnected-(J2-HDMI1_CLK_P-Pad164)") (class "Default")
      (node (ref "J2") (pin "164") (pinfunction "HDMI1_CLK_P_164") (pintype "passive"))
    )
    (net (code "152") (name "unconnected-(J2-HDMI1_HOTPLUG-Pad143)") (class "Default")
      (node (ref "J2") (pin "143") (pinfunction "HDMI1_HOTPLUG_143") (pintype "passive"))
    )
    (net (code "153") (name "unconnected-(J2-HDMI1_SCL-Pad147)") (class "Default")
      (node (ref "J2") (pin "147") (pinfunction "HDMI1_SCL_147") (pintype "passive"))
    )
    (net (code "154") (name "unconnected-(J2-HDMI1_SDA-Pad145)") (class "Default")
      (node (ref "J2") (pin "145") (pinfunction "HDMI1_SDA_145") (pintype "passive"))
    )
    (net (code "155") (name "unconnected-(J2-HDMI1_TX0_N-Pad160)") (class "Default")
      (node (ref "J2") (pin "160") (pinfunction "HDMI1_TX0_N_160") (pintype "passive"))
    )
    (net (code "156") (name "unconnected-(J2-HDMI1_TX0_P-Pad158)") (class "Default")
      (node (ref "J2") (pin "158") (pinfunction "HDMI1_TX0_P_158") (pintype "passive"))
    )
    (net (code "157") (name "unconnected-(J2-HDMI1_TX1_N-Pad154)") (class "Default")
      (node (ref "J2") (pin "154") (pinfunction "HDMI1_TX1_N_154") (pintype "passive"))
    )
    (net (code "158") (name "unconnected-(J2-HDMI1_TX1_P-Pad152)") (class "Default")
      (node (ref "J2") (pin "152") (pinfunction "HDMI1_TX1_P_152") (pintype "passive"))
    )
    (net (code "159") (name "unconnected-(J2-HDMI1_TX2_N-Pad148)") (class "Default")
      (node (ref "J2") (pin "148") (pinfunction "HDMI1_TX2_N_148") (pintype "passive"))
    )
    (net (code "160") (name "unconnected-(J2-HDMI1_TX2_P-Pad146)") (class "Default")
      (node (ref "J2") (pin "146") (pinfunction "HDMI1_TX2_P_146") (pintype "passive"))
    )
    (net (code "161") (name "unconnected-(J2-Reserved-Pad104)") (class "Default")
      (node (ref "J2") (pin "104") (pinfunction "Reserved_104") (pintype "passive"))
    )
    (net (code "162") (name "unconnected-(J2-Reserved-Pad106)") (class "Default")
      (node (ref "J2") (pin "106") (pinfunction "Reserved_106") (pintype "passive"))
    )
    (net (code "163") (name "unconnected-(J2-VDAC_COMP-Pad111)") (class "Default")
      (node (ref "J2") (pin "111") (pinfunction "VDAC_COMP_111") (pintype "passive"))
    )
  )
)
